# Max706.net
KiCad netlist of a schematic drawn in Altium Designer
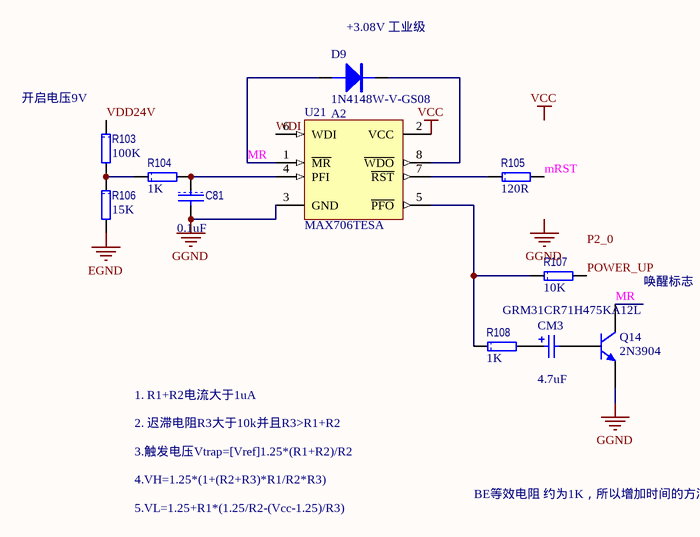
[diagram p0: 上电唤醒_Max706.SchDoc]

(export (version "E")
  (design (tool "Eeschema 10.0.6"))
  (components
    (comp (ref "C81")
      (value "0.1uF")
      (footprint "1608[0603]C")
      (description "多层陶瓷电容器MLCC - SMD/SMT 0603 0.1uF 50volts X7R 10%")
      (fields (field (name "MANUFACTURER") "TDK") (field (name "MANUFACTURER PART NUMBER") "C1608X7R1H104K"))
      (libsource (lib "*") (part "CAP"))
    )
    (comp (ref "CM3")
      (value "GRM31CR71H475KA12L")
      (footprint "3216[1206]C")
      (description "多层陶瓷电容器MLCC - SMD/SMT 4.7uF 50Volts 10%")
      (fields (field (name "MANUFACTURER") "Murata Electronics") (field (name "ALTIUM_VALUE") "4.7uF"))
      (libsource (lib "Miscellaneous Devices") (part "Cap Pol2"))
    )
    (comp (ref "D9")
      (value "1N4148W-V-GS08")
      (footprint "SOD123")
      (description "二极管 - 通用，功率，开关 100V Io/150mA")
      (fields (field (name "MANUFACTURER") "Vishay Semiconductors") (field (name "ALTIUM_VALUE") "A2"))
      (libsource (lib "IN4148") (part "1N4148W"))
    )
    (comp (ref "Q14")
      (value "2N3904")
      (footprint "SOT23_N")
      (description "NPN General Purpose Amplifier")
      (fields (field (name "PUBLISHER") "Altium Limited"))
      (libsource (lib "Miscellaneous Devices") (part "2N3904"))
    )
    (comp (ref "R103")
      (value "100K")
      (footprint "1608[0603]R")
      (description "厚膜电阻器 - SMD 1/10watt 100Kohms 1%")
      (fields
        (field (name "MANUFACTURER") "Vishay / Dale")
        (field (name "MANUFACTURER PART NUMBER") "CRCW0603100KFKEA")
      )
      (libsource (lib "100K 1%") (part "RES"))
    )
    (comp (ref "R104")
      (value "1K")
      (footprint "1608[0603]R")
      (description "厚膜电阻器 - SMD 1/10watt 1.0Kohms 1%")
      (fields
        (field (name "MANUFACTURER") "Vishay / Dale")
        (field (name "MANUFACTURER PART NUMBER") "CRCW06031K00FKEA")
      )
      (libsource (lib "1K 1%") (part "RES"))
    )
    (comp (ref "R105")
      (value "120R")
      (footprint "1608[0603]R")
      (description "厚膜电阻器 - SMD 1/10watt 120ohms 1%")
      (fields
        (field (name "MANUFACTURER") "Vishay / Dale")
        (field (name "MANUFACTURER PART NUMBER") "CRCW0603120RFKEA")
      )
      (libsource (lib "120R 1%") (part "RES"))
    )
    (comp (ref "R106")
      (value "15K")
      (footprint "1608[0603]R")
      (description "厚膜电阻器 - SMD 1/10watt 15Kohms 1%")
      (fields (field (name "Comment") "CRCW060315K0FKEA"))
      (libsource (lib "100K 1%") (part "RES"))
    )
    (comp (ref "R107")
      (value "10K")
      (footprint "1608[0603]R")
      (description "厚膜电阻器 - SMD 1/10watt 10Kohms 1%")
      (fields (field (name "Comment") "CRCW060310KFKEA"))
      (libsource (lib "100K 1%") (part "RES"))
    )
    (comp (ref "R108")
      (value "1K")
      (footprint "1608[0603]R")
      (description "厚膜电阻器 - SMD 1/10watt 1.0Kohms 1%")
      (fields
        (field (name "MANUFACTURER") "Vishay / Dale")
        (field (name "MANUFACTURER PART NUMBER") "CRCW06031K00FKEA")
      )
      (libsource (lib "1K 1%") (part "RES"))
    )
    (comp (ref "U21")
      (value "MAX706TESA")
      (footprint "NSO8_N")
      (description "+3V Voltage Monitoring, Low-Cost, µP Supervisory Circuit")
      (fields (field (name "PUBLISHER") "Altium Limited"))
      (libsource (lib "Maxim Power Mgt Supervisory Circuit") (part "MAX706TESA"))
    )
  )
  (nets
    (net (code "1") (name "/MR") (class "Default")
      (node (ref "D9") (pin "1") (pinfunction "A_1") (pintype "passive"))
      (node (ref "Q14") (pin "3") (pinfunction "C_3") (pintype "passive"))
      (node (ref "U21") (pin "1") (pinfunction "~{MR}_1") (pintype "input"))
    )
    (net (code "3") (name "/POWER_UP") (class "Default")
      (node (ref "R107") (pin "2") (pinfunction "2_2") (pintype "passive"))
    )
    (net (code "4") (name "/VDD24V") (class "Default")
      (node (ref "R103") (pin "1") (pinfunction "1_1") (pintype "passive"))
    )
    (net (code "5") (name "/WDI") (class "Default")
      (node (ref "U21") (pin "6") (pinfunction "WDI_6") (pintype "input"))
    )
    (net (code "6") (name "/mRST") (class "Default")
      (node (ref "R105") (pin "2") (pinfunction "2_2") (pintype "passive"))
    )
    (net (code "7") (name "EGND") (class "Default")
      (node (ref "R106") (pin "2") (pinfunction "2_2") (pintype "passive"))
    )
    (net (code "8") (name "GGND") (class "Default")
      (node (ref "C81") (pin "2") (pinfunction "2_2") (pintype "passive"))
      (node (ref "Q14") (pin "1") (pinfunction "E_1") (pintype "passive"))
      (node (ref "U21") (pin "3") (pinfunction "GND_3") (pintype "power_in"))
    )
    (net (code "9") (name "Net-(CM3-Pad1)") (class "Default")
      (node (ref "CM3") (pin "1") (pinfunction "1_1") (pintype "passive"))
      (node (ref "R108") (pin "2") (pinfunction "2_2") (pintype "passive"))
    )
    (net (code "10") (name "Net-(D9-K)") (class "Default")
      (node (ref "D9") (pin "2") (pinfunction "K_2") (pintype "passive"))
      (node (ref "U21") (pin "8") (pinfunction "~{WDO}_8") (pintype "output"))
    )
    (net (code "11") (name "Net-(Q14-B)") (class "Default")
      (node (ref "CM3") (pin "2") (pinfunction "2_2") (pintype "passive"))
      (node (ref "Q14") (pin "2") (pinfunction "B_2") (pintype "passive"))
    )
    (net (code "12") (name "Net-(R103-Pad2)") (class "Default")
      (node (ref "R103") (pin "2") (pinfunction "2_2") (pintype "passive"))
      (node (ref "R104") (pin "1") (pinfunction "1_1") (pintype "passive"))
      (node (ref "R106") (pin "1") (pinfunction "1_1") (pintype "passive"))
    )
    (net (code "13") (name "Net-(U21-PFI)") (class "Default")
      (node (ref "C81") (pin "1") (pinfunction "1_1") (pintype "passive"))
      (node (ref "R104") (pin "2") (pinfunction "2_2") (pintype "passive"))
      (node (ref "U21") (pin "4") (pinfunction "PFI_4") (pintype "input"))
    )
    (net (code "14") (name "Net-(U21-~{PFO})") (class "Default")
      (node (ref "R107") (pin "1") (pinfunction "1_1") (pintype "passive"))
      (node (ref "R108") (pin "1") (pinfunction "1_1") (pintype "passive"))
      (node (ref "U21") (pin "5") (pinfunction "~{PFO}_5") (pintype "output"))
    )
    (net (code "15") (name "Net-(U21-~{RST})") (class "Default")
      (node (ref "R105") (pin "1") (pinfunction "1_1") (pintype "passive"))
      (node (ref "U21") (pin "7") (pinfunction "~{RST}_7") (pintype "output"))
    )
    (net (code "16") (name "VCC") (class "Default")
      (node (ref "U21") (pin "2") (pinfunction "VCC_2") (pintype "power_in"))
    )
  )
)
